# Schematic.net
KiCad netlist of a schematic drawn in Altium Designer
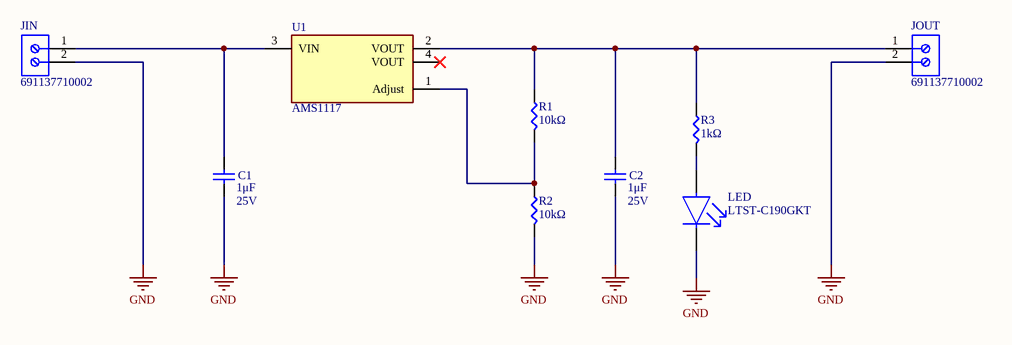
[diagram p0: Schematic.SchDoc]

(export (version "E")
  (design (tool "Eeschema 10.0.6"))
  (components
    (comp (ref "C1")
      (value "1μF")
      (footprint "CAP0805")
      (description "CAP CER 1UF 25V X7R 0805")
      (fields (field (name "VOLTAGE RATING") "25V") (field (name "Comment") "GCM21BR71E105KA56L"))
      (libsource (lib "Bootcamp_Schematic_Library") (part "GCM21BR71E105KA56L"))
    )
    (comp (ref "C2")
      (value "1μF")
      (footprint "CAP0805")
      (description "CAP CER 1UF 25V X7R 0805")
      (fields (field (name "VOLTAGE RATING") "25V") (field (name "Comment") "GCM21BR71E105KA56L"))
      (libsource (lib "Bootcamp_Schematic_Library") (part "GCM21BR71E105KA56L"))
    )
    (comp (ref "JIN")
      (value "691137710002")
      (footprint "691137710002")
      (libsource (lib "Altium Content Vault") (part "TBL - 1R - 02P - Screw"))
    )
    (comp (ref "JOUT")
      (value "691137710002")
      (footprint "691137710002")
      (libsource (lib "Altium Content Vault") (part "TBL - 1R - 02P - Screw"))
    )
    (comp (ref "LED")
      (value "LTST-C190GKT")
      (footprint "FP-LTST-C190GKT-MFG")
      (description "LED GREEN CLEAR CHIP SMD")
      (fields (field (name "VOLTAGE") "2V"))
      (libsource (lib "Altium Content Vault") (part "8706943c75ba83719d021d2fdc84c58"))
    )
    (comp (ref "R1")
      (value "10kΩ")
      (footprint "RES0603")
      (description "RES 10K OHM 1% 1/8W 0603")
      (fields (field (name "Comment") "RNCP0603FTD10K0"))
      (libsource (lib "Bootcamp_Schematic_Library") (part "RNCP0603FTD10K0"))
    )
    (comp (ref "R2")
      (value "10kΩ")
      (footprint "RES0603")
      (description "RES 10K OHM 1% 1/8W 0603")
      (fields (field (name "Comment") "RNCP0603FTD10K0"))
      (libsource (lib "Bootcamp_Schematic_Library") (part "RNCP0603FTD10K0"))
    )
    (comp (ref "R3")
      (value "1kΩ")
      (footprint "RES0603")
      (description "RES 10K OHM 1% 1/8W 0603")
      (fields (field (name "Comment") "RNCP0603FTD10K0"))
      (libsource (lib "Bootcamp_Schematic_Library") (part "RNCP0603FTD10K0"))
    )
    (comp (ref "U1")
      (value "AMS1117")
      (footprint "FP-ams1117-IPC_C")
      (description "1A LOW DROPOUT VOLTAGE REGULATOR")
      (libsource (lib "Altium Content Vault") (part "59ad430b93a2c51b3e6ee7c3b069677"))
    )
  )
  (nets
    (net (code "1") (name "GND") (class "Default")
      (node (ref "C1") (pin "1") (pinfunction "1_1") (pintype "passive"))
      (node (ref "C2") (pin "1") (pinfunction "1_1") (pintype "passive"))
      (node (ref "JIN") (pin "2") (pinfunction "2_2") (pintype "passive"))
      (node (ref "JOUT") (pin "2") (pinfunction "2_2") (pintype "passive"))
      (node (ref "LED") (pin "1") (pinfunction "C_1") (pintype "passive"))
      (node (ref "R2") (pin "1") (pinfunction "1_1") (pintype "passive"))
    )
    (net (code "2") (name "Net-(C2-Pad2)") (class "Default")
      (node (ref "C2") (pin "2") (pinfunction "2_2") (pintype "passive"))
      (node (ref "JOUT") (pin "1") (pinfunction "1_1") (pintype "passive"))
      (node (ref "R1") (pin "2") (pinfunction "2_2") (pintype "passive"))
      (node (ref "R3") (pin "2") (pinfunction "2_2") (pintype "passive"))
      (node (ref "U1") (pin "2") (pinfunction "VOUT_2") (pintype "passive"))
    )
    (net (code "3") (name "Net-(LED-A)") (class "Default")
      (node (ref "LED") (pin "2") (pinfunction "A_2") (pintype "passive"))
      (node (ref "R3") (pin "1") (pinfunction "1_1") (pintype "passive"))
    )
    (net (code "4") (name "Net-(U1-Adjust)") (class "Default")
      (node (ref "R1") (pin "1") (pinfunction "1_1") (pintype "passive"))
      (node (ref "R2") (pin "2") (pinfunction "2_2") (pintype "passive"))
      (node (ref "U1") (pin "1") (pinfunction "Adjust_1") (pintype "passive"))
    )
    (net (code "5") (name "Net-(U1-VIN)") (class "Default")
      (node (ref "C1") (pin "2") (pinfunction "2_2") (pintype "passive"))
      (node (ref "JIN") (pin "1") (pinfunction "1_1") (pintype "passive"))
      (node (ref "U1") (pin "3") (pinfunction "VIN_3") (pintype "power_in"))
    )
    (net (code "6") (name "unconnected-(U1-VOUT-Pad4)") (class "Default")
      (node (ref "U1") (pin "4") (pinfunction "VOUT_4") (pintype "passive+no_connect"))
    )
  )
)
